# Casillero.net
KiCad netlist of a schematic drawn in EAGLE
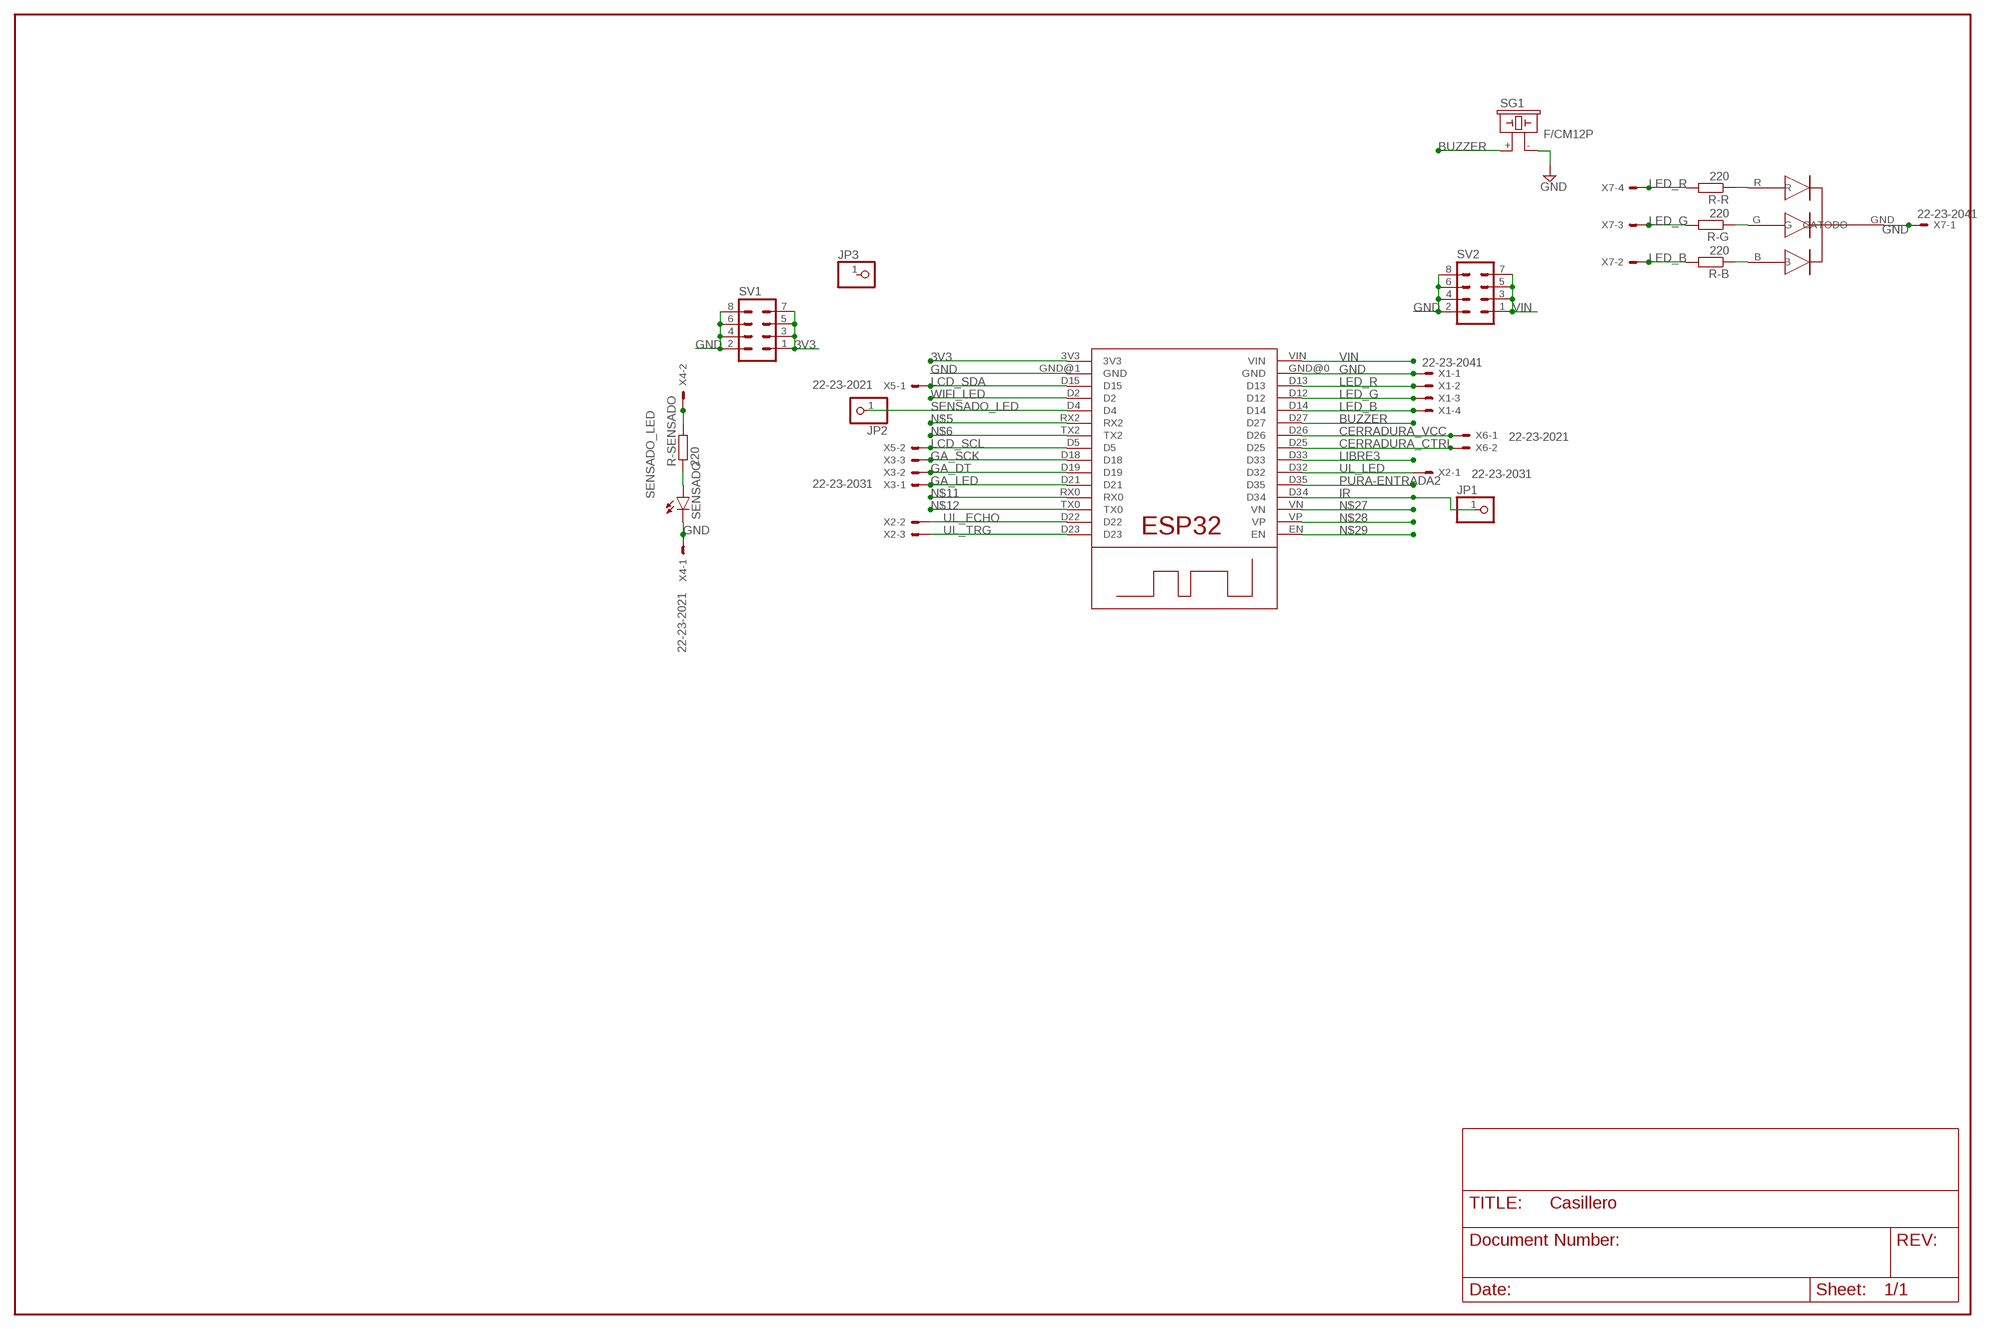
[diagram p0: schematic, sheet 1]

(export (version "E")
  (design (tool "Eeschema 10.0.6"))
  (components
    (comp (ref "JP1")
      (value "PINHD-1X1")
      (footprint "eagle-import:1X01")
      (libsource (lib "eagle-import") (part "PINHD-1X1"))
    )
    (comp (ref "JP2")
      (value "PINHD-1X1")
      (footprint "eagle-import:1X01")
      (libsource (lib "eagle-import") (part "PINHD-1X1"))
    )
    (comp (ref "JP3")
      (value "PINHD-1X1")
      (footprint "eagle-import:1X01")
      (libsource (lib "eagle-import") (part "PINHD-1X1"))
    )
    (comp (ref "R-B")
      (value "220")
      (footprint "eagle-import:0204_7")
      (libsource (lib "eagle-import") (part "R-EU_0204/7"))
    )
    (comp (ref "R-G")
      (value "220")
      (footprint "eagle-import:0204_7")
      (libsource (lib "eagle-import") (part "R-EU_0204/7"))
    )
    (comp (ref "R-R")
      (value "220")
      (footprint "eagle-import:0204_7")
      (libsource (lib "eagle-import") (part "R-EU_0204/7"))
    )
    (comp (ref "R-SENSADO")
      (value "220")
      (footprint "eagle-import:0204_7")
      (libsource (lib "eagle-import") (part "R-EU_0204/7"))
    )
    (comp (ref "SENSADO")
      (value "LED3MM")
      (footprint "eagle-import:LED3MM")
      (libsource (lib "eagle-import") (part "LED3MM"))
    )
    (comp (ref "SG1")
      (value "F/CM12P")
      (footprint "eagle-import:F_CM12P")
      (libsource (lib "eagle-import") (part "F/CM12P"))
    )
    (comp (ref "SV1")
      (value "MA04-2")
      (footprint "eagle-import:MA04-2")
      (libsource (lib "eagle-import") (part "MA04-2"))
    )
    (comp (ref "SV2")
      (value "MA04-2")
      (footprint "eagle-import:MA04-2")
      (libsource (lib "eagle-import") (part "MA04-2"))
    )
    (comp (ref "U$1")
      (value "ESP32WROOM")
      (footprint "eagle-import:ESP32WROOM")
      (libsource (lib "eagle-import") (part "ESP32WROOM"))
    )
    (comp (ref "U$3")
      (value "LEDRGB")
      (footprint "eagle-import:LEDRGB")
      (libsource (lib "eagle-import") (part "LEDRGB"))
    )
    (comp (ref "X1")
      (value "22-23-2041")
      (footprint "eagle-import:22-23-2041")
      (fields (field (name "MF") "MOLEX"))
      (libsource (lib "eagle-import") (part "22-23-2041"))
    )
    (comp (ref "X2")
      (value "22-23-2031")
      (footprint "eagle-import:22-23-2031")
      (fields (field (name "MF") "MOLEX"))
      (libsource (lib "eagle-import") (part "22-23-2031"))
    )
    (comp (ref "X3")
      (value "22-23-2031")
      (footprint "eagle-import:22-23-2031")
      (fields (field (name "MF") "MOLEX"))
      (libsource (lib "eagle-import") (part "22-23-2031"))
    )
    (comp (ref "X4")
      (value "22-23-2021")
      (footprint "eagle-import:22-23-2021")
      (fields (field (name "MF") "MOLEX"))
      (libsource (lib "eagle-import") (part "22-23-2021"))
    )
    (comp (ref "X5")
      (value "22-23-2021")
      (footprint "eagle-import:22-23-2021")
      (fields (field (name "MF") "MOLEX"))
      (libsource (lib "eagle-import") (part "22-23-2021"))
    )
    (comp (ref "X6")
      (value "22-23-2021")
      (footprint "eagle-import:22-23-2021")
      (fields (field (name "MF") "MOLEX"))
      (libsource (lib "eagle-import") (part "22-23-2021"))
    )
    (comp (ref "X7")
      (value "22-23-2041")
      (footprint "eagle-import:22-23-2041")
      (fields (field (name "MF") "MOLEX"))
      (libsource (lib "eagle-import") (part "22-23-2041"))
    )
  )
  (nets
    (net (code "1") (name "/3V3") (class "Default")
      (node (ref "SV1") (pin "1") (pinfunction "1_1") (pintype "passive"))
      (node (ref "SV1") (pin "3") (pinfunction "3_3") (pintype "passive"))
      (node (ref "SV1") (pin "5") (pinfunction "5_5") (pintype "passive"))
      (node (ref "SV1") (pin "7") (pinfunction "7_7") (pintype "passive"))
      (node (ref "U$1") (pin "3V3") (pinfunction "3V3_3V3") (pintype "bidirectional"))
    )
    (net (code "2") (name "/BUZZER") (class "Default")
      (node (ref "SG1") (pin "+") (pinfunction "1_+") (pintype "passive"))
      (node (ref "U$1") (pin "D27") (pinfunction "D27_D27") (pintype "bidirectional"))
    )
    (net (code "3") (name "/CERRADURA_CTRL") (class "Default")
      (node (ref "U$1") (pin "D25") (pinfunction "D25_D25") (pintype "bidirectional"))
      (node (ref "X6") (pin "2") (pinfunction "S_2") (pintype "passive"))
    )
    (net (code "4") (name "/CERRADURA_VCC") (class "Default")
      (node (ref "U$1") (pin "D26") (pinfunction "D26_D26") (pintype "bidirectional"))
      (node (ref "X6") (pin "1") (pinfunction "S_1") (pintype "passive"))
    )
    (net (code "5") (name "/GA_DT") (class "Default")
      (node (ref "U$1") (pin "D19") (pinfunction "D19_D19") (pintype "bidirectional"))
      (node (ref "X3") (pin "2") (pinfunction "S_2") (pintype "passive"))
    )
    (net (code "6") (name "/GA_LED") (class "Default")
      (node (ref "U$1") (pin "D21") (pinfunction "D21_D21") (pintype "bidirectional"))
      (node (ref "X3") (pin "1") (pinfunction "S_1") (pintype "passive"))
    )
    (net (code "7") (name "/GA_SCK") (class "Default")
      (node (ref "U$1") (pin "D18") (pinfunction "D18_D18") (pintype "bidirectional"))
      (node (ref "X3") (pin "3") (pinfunction "S_3") (pintype "passive"))
    )
    (net (code "8") (name "/IR") (class "Default")
      (node (ref "JP1") (pin "1") (pinfunction "1_1") (pintype "passive"))
      (node (ref "U$1") (pin "D34") (pinfunction "D34_D34") (pintype "bidirectional"))
    )
    (net (code "9") (name "/LCD_SCL") (class "Default")
      (node (ref "U$1") (pin "D5") (pinfunction "D5_D5") (pintype "bidirectional"))
      (node (ref "X5") (pin "2") (pinfunction "S_2") (pintype "passive"))
    )
    (net (code "10") (name "/LCD_SDA") (class "Default")
      (node (ref "U$1") (pin "D15") (pinfunction "D15_D15") (pintype "bidirectional"))
      (node (ref "X5") (pin "1") (pinfunction "S_1") (pintype "passive"))
    )
    (net (code "11") (name "/LED_B") (class "Default")
      (node (ref "R-B") (pin "2") (pinfunction "2_2") (pintype "passive"))
      (node (ref "U$1") (pin "D14") (pinfunction "D14_D14") (pintype "bidirectional"))
      (node (ref "X1") (pin "4") (pinfunction "S_4") (pintype "passive"))
      (node (ref "X7") (pin "2") (pinfunction "S_2") (pintype "passive"))
    )
    (net (code "12") (name "/LED_G") (class "Default")
      (node (ref "R-G") (pin "2") (pinfunction "2_2") (pintype "passive"))
      (node (ref "U$1") (pin "D12") (pinfunction "D12_D12") (pintype "bidirectional"))
      (node (ref "X1") (pin "3") (pinfunction "S_3") (pintype "passive"))
      (node (ref "X7") (pin "3") (pinfunction "S_3") (pintype "passive"))
    )
    (net (code "13") (name "/LED_R") (class "Default")
      (node (ref "R-R") (pin "2") (pinfunction "2_2") (pintype "passive"))
      (node (ref "U$1") (pin "D13") (pinfunction "D13_D13") (pintype "bidirectional"))
      (node (ref "X1") (pin "2") (pinfunction "S_2") (pintype "passive"))
      (node (ref "X7") (pin "4") (pinfunction "S_4") (pintype "passive"))
    )
    (net (code "14") (name "/LIBRE3") (class "Default")
      (node (ref "U$1") (pin "D33") (pinfunction "D33_D33") (pintype "bidirectional"))
    )
    (net (code "15") (name "/N$5") (class "Default")
      (node (ref "U$1") (pin "RX2") (pinfunction "RX2_RX2") (pintype "bidirectional"))
    )
    (net (code "16") (name "/N$6") (class "Default")
      (node (ref "U$1") (pin "TX2") (pinfunction "TX2_TX2") (pintype "bidirectional"))
    )
    (net (code "17") (name "/N$11") (class "Default")
      (node (ref "U$1") (pin "RX0") (pinfunction "RX0_RX0") (pintype "bidirectional"))
    )
    (net (code "18") (name "/N$12") (class "Default")
      (node (ref "U$1") (pin "TX0") (pinfunction "TX0_TX0") (pintype "bidirectional"))
    )
    (net (code "19") (name "/N$27") (class "Default")
      (node (ref "U$1") (pin "VN") (pinfunction "VN_VN") (pintype "bidirectional"))
    )
    (net (code "20") (name "/N$28") (class "Default")
      (node (ref "U$1") (pin "VP") (pinfunction "VP_VP") (pintype "bidirectional"))
    )
    (net (code "21") (name "/N$29") (class "Default")
      (node (ref "U$1") (pin "EN") (pinfunction "EN_EN") (pintype "bidirectional"))
    )
    (net (code "22") (name "/PURA-ENTRADA2") (class "Default")
      (node (ref "U$1") (pin "D35") (pinfunction "D35_D35") (pintype "bidirectional"))
    )
    (net (code "23") (name "/SENSADO_LED") (class "Default")
      (node (ref "JP2") (pin "1") (pinfunction "1_1") (pintype "passive"))
      (node (ref "R-SENSADO") (pin "2") (pinfunction "2_2") (pintype "passive"))
      (node (ref "U$1") (pin "D4") (pinfunction "D4_D4") (pintype "bidirectional"))
      (node (ref "X4") (pin "2") (pinfunction "S_2") (pintype "passive"))
    )
    (net (code "24") (name "/UL_ECHO") (class "Default")
      (node (ref "U$1") (pin "D22") (pinfunction "D22_D22") (pintype "bidirectional"))
      (node (ref "X2") (pin "2") (pinfunction "S_2") (pintype "passive"))
    )
    (net (code "25") (name "/UL_LED") (class "Default")
      (node (ref "U$1") (pin "D32") (pinfunction "D32_D32") (pintype "bidirectional"))
      (node (ref "X2") (pin "1") (pinfunction "S_1") (pintype "passive"))
    )
    (net (code "26") (name "/UL_TRG") (class "Default")
      (node (ref "U$1") (pin "D23") (pinfunction "D23_D23") (pintype "bidirectional"))
      (node (ref "X2") (pin "3") (pinfunction "S_3") (pintype "passive"))
    )
    (net (code "27") (name "/VIN") (class "Default")
      (node (ref "SV2") (pin "1") (pinfunction "1_1") (pintype "passive"))
      (node (ref "SV2") (pin "3") (pinfunction "3_3") (pintype "passive"))
      (node (ref "SV2") (pin "5") (pinfunction "5_5") (pintype "passive"))
      (node (ref "SV2") (pin "7") (pinfunction "7_7") (pintype "passive"))
      (node (ref "U$1") (pin "VIN") (pinfunction "VIN_VIN") (pintype "bidirectional"))
    )
    (net (code "28") (name "/WIFI_LED") (class "Default")
      (node (ref "U$1") (pin "D2") (pinfunction "D2_D2") (pintype "bidirectional"))
    )
    (net (code "29") (name "GND") (class "Default")
      (node (ref "SENSADO") (pin "K") (pinfunction "C_K") (pintype "passive"))
      (node (ref "SG1") (pin "-") (pinfunction "2_-") (pintype "passive"))
      (node (ref "SV1") (pin "2") (pinfunction "2_2") (pintype "passive"))
      (node (ref "SV1") (pin "4") (pinfunction "4_4") (pintype "passive"))
      (node (ref "SV1") (pin "6") (pinfunction "6_6") (pintype "passive"))
      (node (ref "SV1") (pin "8") (pinfunction "8_8") (pintype "passive"))
      (node (ref "SV2") (pin "2") (pinfunction "2_2") (pintype "passive"))
      (node (ref "SV2") (pin "4") (pinfunction "4_4") (pintype "passive"))
      (node (ref "SV2") (pin "6") (pinfunction "6_6") (pintype "passive"))
      (node (ref "SV2") (pin "8") (pinfunction "8_8") (pintype "passive"))
      (node (ref "U$1") (pin "GND@0") (pinfunction "GND_GND@0") (pintype "bidirectional"))
      (node (ref "U$1") (pin "GND@1") (pinfunction "GND_GND@1") (pintype "bidirectional"))
      (node (ref "U$3") (pin "GND") (pinfunction "CATODO_GND") (pintype "bidirectional"))
      (node (ref "X1") (pin "1") (pinfunction "S_1") (pintype "passive"))
      (node (ref "X4") (pin "1") (pinfunction "S_1") (pintype "passive"))
      (node (ref "X7") (pin "1") (pinfunction "S_1") (pintype "passive"))
    )
    (net (code "30") (name "Net-(R-B-Pad1)") (class "Default")
      (node (ref "R-B") (pin "1") (pinfunction "1_1") (pintype "passive"))
      (node (ref "U$3") (pin "B") (pinfunction "B_B") (pintype "bidirectional"))
    )
    (net (code "31") (name "Net-(R-G-Pad1)") (class "Default")
      (node (ref "R-G") (pin "1") (pinfunction "1_1") (pintype "passive"))
      (node (ref "U$3") (pin "G") (pinfunction "G_G") (pintype "bidirectional"))
    )
    (net (code "32") (name "Net-(R-R-Pad1)") (class "Default")
      (node (ref "R-R") (pin "1") (pinfunction "1_1") (pintype "passive"))
      (node (ref "U$3") (pin "R") (pinfunction "R_R") (pintype "bidirectional"))
    )
    (net (code "33") (name "Net-(R-SENSADO-Pad1)") (class "Default")
      (node (ref "R-SENSADO") (pin "1") (pinfunction "1_1") (pintype "passive"))
      (node (ref "SENSADO") (pin "A") (pinfunction "A_A") (pintype "passive"))
    )
    (net (code "34") (name "unconnected-(JP3-Pad1)") (class "Default")
      (node (ref "JP3") (pin "1") (pinfunction "1_1") (pintype "passive"))
    )
  )
)
